# WifiModule.net
KiCad netlist of a schematic drawn in Altium Designer
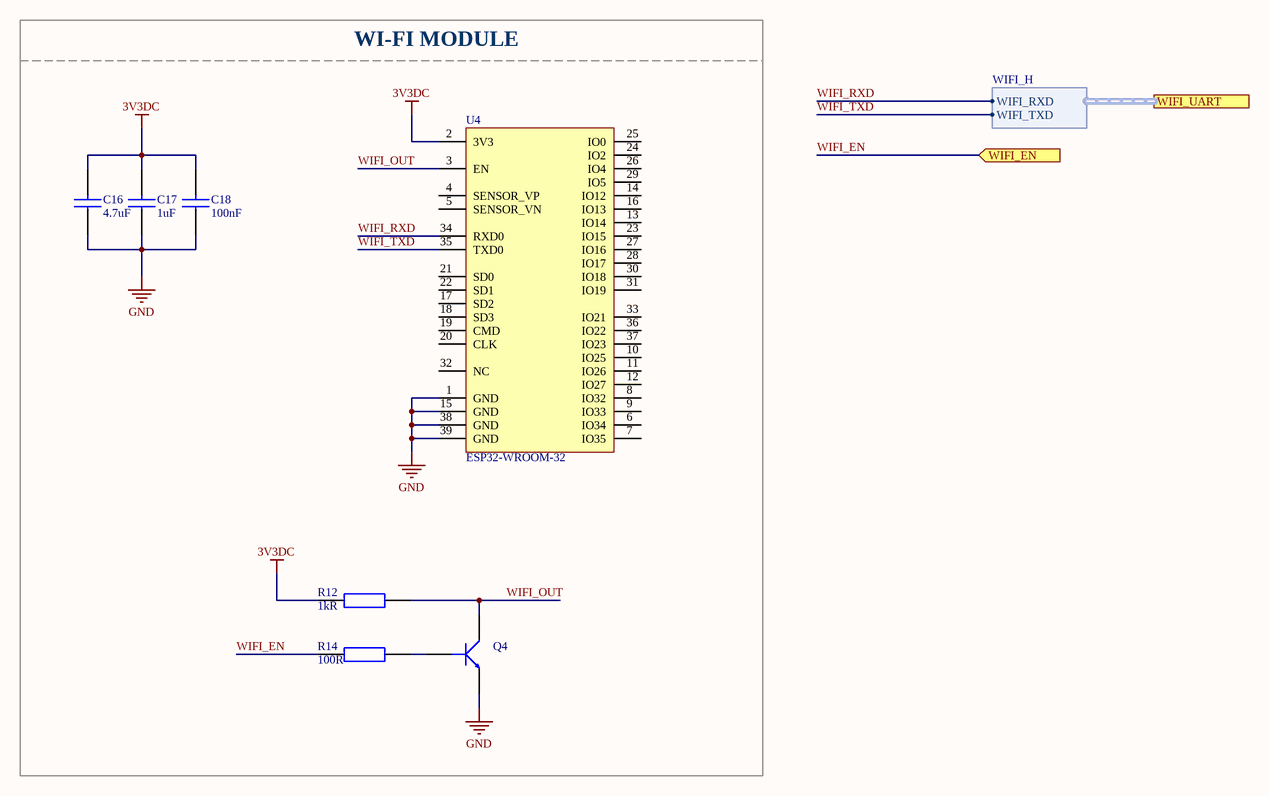
[diagram p0: WifiModule.SchDoc]

(export (version "E")
  (design (tool "Eeschema 10.0.6"))
  (components
    (comp (ref "C16")
      (value "CL21A475KAQNNNE")
      (footprint "CAP_0805")
      (description "CAP CER 4.7uF %10 0805")
      (fields
        (field (name "MANUFACTURER") "Samsung")
        (field (name "TOLERANCE") "10%")
        (field (name "CAPACITANCE") "4.7uF")
        (field (name "DESIGNED BY") "BERK")
      )
      (libsource (lib "GuvenlikSistemi_Library") (part "CAP CER 4.7uF 0805"))
    )
    (comp (ref "C17")
      (value "CL21B105KBFNNNE")
      (footprint "CAP_0805")
      (description "CAP CER 1uF %10 0805")
      (fields
        (field (name "MANUFACTURER") "Samsung")
        (field (name "TOLERANCE") "10%")
        (field (name "CAPACITANCE") "1uF")
        (field (name "DESIGNED BY") "BERK")
      )
      (libsource (lib "GuvenlikSistemi_Library") (part "CAP CER 1uF 0805"))
    )
    (comp (ref "C18")
      (value "CL21B104KBCNNNC")
      (footprint "CAP_0805")
      (description "CAP CER 100nF %10 0805")
      (fields
        (field (name "MANUFACTURER") "Samsung")
        (field (name "TOLERANCE") "10%")
        (field (name "CAPACITANCE") "100nF")
        (field (name "DESIGNED BY") "BERK")
      )
      (libsource (lib "GuvenlikSistemi_Library") (part "CAP CER 100nF 0805"))
    )
    (comp (ref "Q4")
      (value "MMBT3904-7-F")
      (footprint "SOT-23F")
      (description "Transistor General Purpose BJT NPN 40 Volt 0.2A Automotive 3-Pin SOT-23")
      (fields (field (name "MANUFACTURER") "Diodes Zetex") (field (name "DESIGNED BY") "BERK"))
      (libsource (lib "GuvenlikSistemi_Library") (part "MMBT3904-7-F"))
    )
    (comp (ref "R12")
      (value "RC0603FR-0710KL")
      (footprint "RES_0603")
      (description "RES 1K %1 OHM 0603 SMD")
      (fields
        (field (name "MANUFACTURER") "Yageo")
        (field (name "MANUFACTURER PART NUMBER") "RC0603JR-071KL")
        (field (name "RESISTANCE") "1kR")
        (field (name "DESIGNED BY") "BERK")
      )
      (libsource (lib "GuvenlikSistemi_Library") (part "RES 1K OHM 0603"))
    )
    (comp (ref "R14")
      (value "RC0603JR-07100RL")
      (footprint "RES_0603")
      (description "RES 100 %5 OHM 0603 SMD")
      (fields
        (field (name "MANUFACTURER") "Yageo")
        (field (name "TOLERANCE") "5%")
        (field (name "RESISTANCE") "100R")
        (field (name "DESIGNED BY") "BERK")
      )
      (libsource (lib "GuvenlikSistemi_Library") (part "RES 100 OHM 0603"))
    )
    (comp (ref "U4")
      (value "ESP32-WROOM-32")
      (footprint "ESP32-32")
      (description "SMD MODULE, ESP32-D0WDQ6, 32MBIT")
      (fields (field (name "MANUFACTURER") "Espressif Systems") (field (name "DESIGNED BY") "BERK"))
      (libsource (lib "GuvenlikSistemi_Library") (part "ESP32-WROOM-32"))
    )
  )
  (nets
    (net (code "2") (name "/WIFI_EN") (class "Default")
      (node (ref "R14") (pin "1") (pinfunction "1_1") (pintype "passive"))
    )
    (net (code "3") (name "/WIFI_OUT") (class "Default")
      (node (ref "Q4") (pin "3") (pinfunction "C_3") (pintype "power_in"))
      (node (ref "R12") (pin "1") (pinfunction "1_1") (pintype "passive"))
      (node (ref "U4") (pin "3") (pinfunction "EN_3") (pintype "passive"))
    )
    (net (code "4") (name "/WIFI_RXD") (class "Default")
      (node (ref "U4") (pin "34") (pinfunction "RXD0_34") (pintype "passive"))
    )
    (net (code "5") (name "/WIFI_TXD") (class "Default")
      (node (ref "U4") (pin "35") (pinfunction "TXD0_35") (pintype "passive"))
    )
    (net (code "7") (name "3V3DC") (class "Default")
      (node (ref "C16") (pin "2") (pinfunction "2_2") (pintype "passive"))
      (node (ref "C17") (pin "2") (pinfunction "2_2") (pintype "passive"))
      (node (ref "C18") (pin "2") (pinfunction "2_2") (pintype "passive"))
      (node (ref "R12") (pin "2") (pinfunction "2_2") (pintype "passive"))
      (node (ref "U4") (pin "2") (pinfunction "3V3_2") (pintype "passive"))
    )
    (net (code "8") (name "GND") (class "Default")
      (node (ref "C16") (pin "1") (pinfunction "1_1") (pintype "passive"))
      (node (ref "C17") (pin "1") (pinfunction "1_1") (pintype "passive"))
      (node (ref "C18") (pin "1") (pinfunction "1_1") (pintype "passive"))
      (node (ref "Q4") (pin "2") (pinfunction "E_2") (pintype "power_in"))
      (node (ref "U4") (pin "1") (pinfunction "GND_1") (pintype "passive"))
      (node (ref "U4") (pin "15") (pinfunction "GND_15") (pintype "passive"))
      (node (ref "U4") (pin "38") (pinfunction "GND_38") (pintype "passive"))
      (node (ref "U4") (pin "39") (pinfunction "GND_39") (pintype "passive"))
    )
    (net (code "9") (name "Net-(Q4-B)") (class "Default")
      (node (ref "Q4") (pin "1") (pinfunction "B_1") (pintype "power_in"))
      (node (ref "R14") (pin "2") (pinfunction "2_2") (pintype "passive"))
    )
    (net (code "10") (name "unconnected-(U4-CLK-Pad20)") (class "Default")
      (node (ref "U4") (pin "20") (pinfunction "CLK_20") (pintype "passive"))
    )
    (net (code "11") (name "unconnected-(U4-CMD-Pad19)") (class "Default")
      (node (ref "U4") (pin "19") (pinfunction "CMD_19") (pintype "passive"))
    )
    (net (code "12") (name "unconnected-(U4-IO0-Pad25)") (class "Default")
      (node (ref "U4") (pin "25") (pinfunction "IO0_25") (pintype "passive"))
    )
    (net (code "13") (name "unconnected-(U4-IO2-Pad24)") (class "Default")
      (node (ref "U4") (pin "24") (pinfunction "IO2_24") (pintype "passive"))
    )
    (net (code "14") (name "unconnected-(U4-IO4-Pad26)") (class "Default")
      (node (ref "U4") (pin "26") (pinfunction "IO4_26") (pintype "passive"))
    )
    (net (code "15") (name "unconnected-(U4-IO5-Pad29)") (class "Default")
      (node (ref "U4") (pin "29") (pinfunction "IO5_29") (pintype "passive"))
    )
    (net (code "16") (name "unconnected-(U4-IO12-Pad14)") (class "Default")
      (node (ref "U4") (pin "14") (pinfunction "IO12_14") (pintype "passive"))
    )
    (net (code "17") (name "unconnected-(U4-IO13-Pad16)") (class "Default")
      (node (ref "U4") (pin "16") (pinfunction "IO13_16") (pintype "passive"))
    )
    (net (code "18") (name "unconnected-(U4-IO14-Pad13)") (class "Default")
      (node (ref "U4") (pin "13") (pinfunction "IO14_13") (pintype "passive"))
    )
    (net (code "19") (name "unconnected-(U4-IO15-Pad23)") (class "Default")
      (node (ref "U4") (pin "23") (pinfunction "IO15_23") (pintype "passive"))
    )
    (net (code "20") (name "unconnected-(U4-IO16-Pad27)") (class "Default")
      (node (ref "U4") (pin "27") (pinfunction "IO16_27") (pintype "passive"))
    )
    (net (code "21") (name "unconnected-(U4-IO17-Pad28)") (class "Default")
      (node (ref "U4") (pin "28") (pinfunction "IO17_28") (pintype "passive"))
    )
    (net (code "22") (name "unconnected-(U4-IO18-Pad30)") (class "Default")
      (node (ref "U4") (pin "30") (pinfunction "IO18_30") (pintype "passive"))
    )
    (net (code "23") (name "unconnected-(U4-IO19-Pad31)") (class "Default")
      (node (ref "U4") (pin "31") (pinfunction "IO19_31") (pintype "passive"))
    )
    (net (code "24") (name "unconnected-(U4-IO21-Pad33)") (class "Default")
      (node (ref "U4") (pin "33") (pinfunction "IO21_33") (pintype "passive"))
    )
    (net (code "25") (name "unconnected-(U4-IO22-Pad36)") (class "Default")
      (node (ref "U4") (pin "36") (pinfunction "IO22_36") (pintype "passive"))
    )
    (net (code "26") (name "unconnected-(U4-IO23-Pad37)") (class "Default")
      (node (ref "U4") (pin "37") (pinfunction "IO23_37") (pintype "passive"))
    )
    (net (code "27") (name "unconnected-(U4-IO25-Pad10)") (class "Default")
      (node (ref "U4") (pin "10") (pinfunction "IO25_10") (pintype "passive"))
    )
    (net (code "28") (name "unconnected-(U4-IO26-Pad11)") (class "Default")
      (node (ref "U4") (pin "11") (pinfunction "IO26_11") (pintype "passive"))
    )
    (net (code "29") (name "unconnected-(U4-IO27-Pad12)") (class "Default")
      (node (ref "U4") (pin "12") (pinfunction "IO27_12") (pintype "passive"))
    )
    (net (code "30") (name "unconnected-(U4-IO32-Pad8)") (class "Default")
      (node (ref "U4") (pin "8") (pinfunction "IO32_8") (pintype "passive"))
    )
    (net (code "31") (name "unconnected-(U4-IO33-Pad9)") (class "Default")
      (node (ref "U4") (pin "9") (pinfunction "IO33_9") (pintype "passive"))
    )
    (net (code "32") (name "unconnected-(U4-IO34-Pad6)") (class "Default")
      (node (ref "U4") (pin "6") (pinfunction "IO34_6") (pintype "passive"))
    )
    (net (code "33") (name "unconnected-(U4-IO35-Pad7)") (class "Default")
      (node (ref "U4") (pin "7") (pinfunction "IO35_7") (pintype "passive"))
    )
    (net (code "34") (name "unconnected-(U4-NC-Pad32)") (class "Default")
      (node (ref "U4") (pin "32") (pinfunction "NC_32") (pintype "passive"))
    )
    (net (code "35") (name "unconnected-(U4-SD0-Pad21)") (class "Default")
      (node (ref "U4") (pin "21") (pinfunction "SD0_21") (pintype "passive"))
    )
    (net (code "36") (name "unconnected-(U4-SD1-Pad22)") (class "Default")
      (node (ref "U4") (pin "22") (pinfunction "SD1_22") (pintype "passive"))
    )
    (net (code "37") (name "unconnected-(U4-SD2-Pad17)") (class "Default")
      (node (ref "U4") (pin "17") (pinfunction "SD2_17") (pintype "passive"))
    )
    (net (code "38") (name "unconnected-(U4-SD3-Pad18)") (class "Default")
      (node (ref "U4") (pin "18") (pinfunction "SD3_18") (pintype "passive"))
    )
    (net (code "39") (name "unconnected-(U4-SENSOR_VN-Pad5)") (class "Default")
      (node (ref "U4") (pin "5") (pinfunction "SENSOR_VN_5") (pintype "passive"))
    )
    (net (code "40") (name "unconnected-(U4-SENSOR_VP-Pad4)") (class "Default")
      (node (ref "U4") (pin "4") (pinfunction "SENSOR_VP_4") (pintype "passive"))
    )
  )
)
